# Enclosure_130x95_BP-R.net
KiCad netlist of a schematic drawn in EAGLE
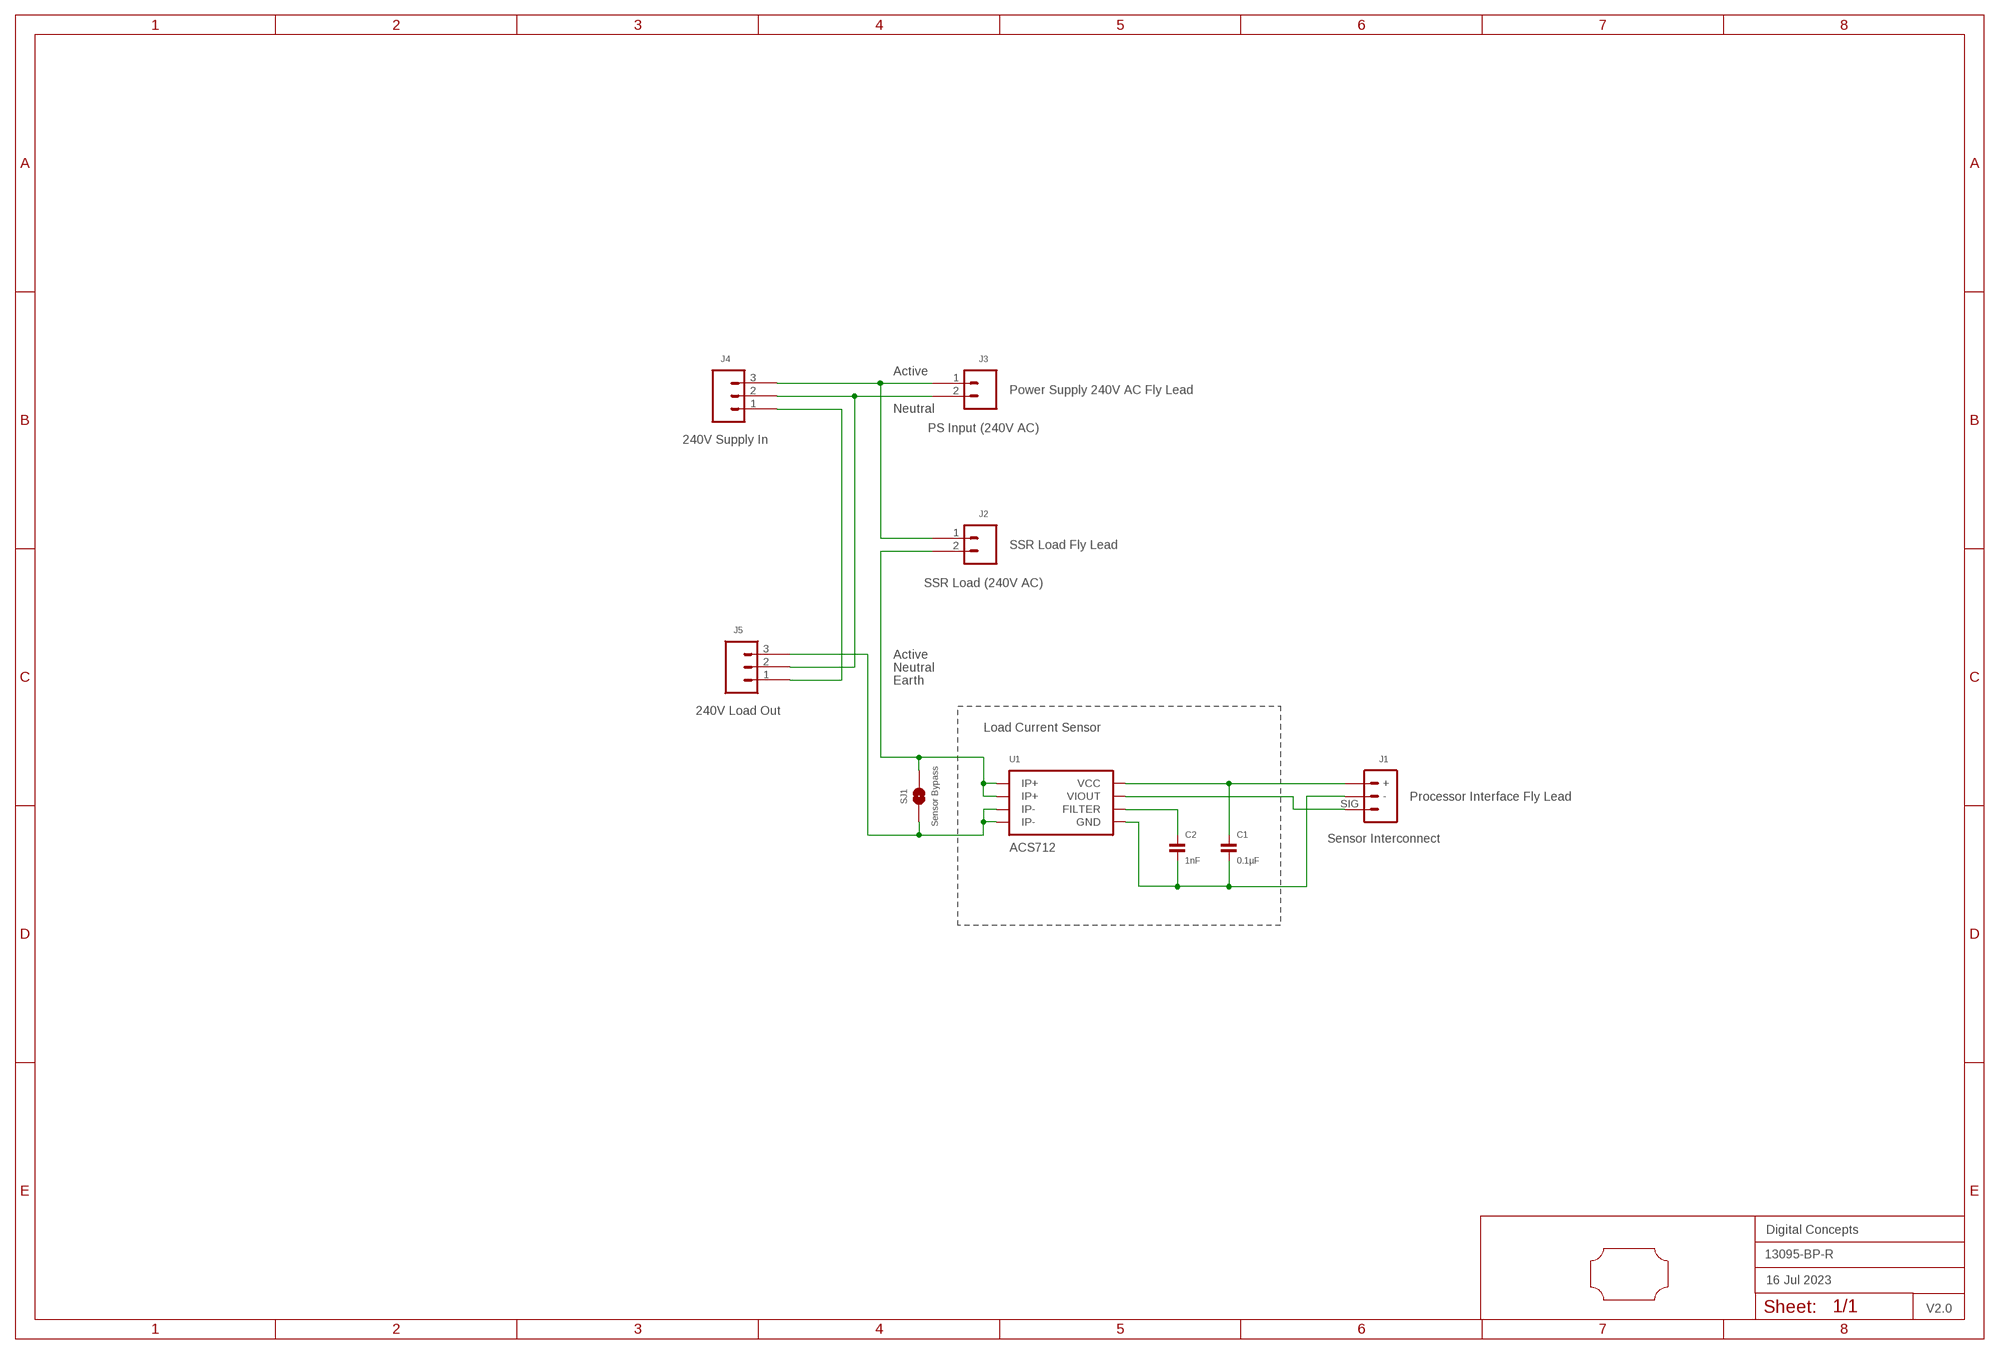
[diagram p0: schematic, sheet 1]

(export (version "E")
  (design (tool "Eeschema 10.0.6"))
  (components
    (comp (ref "C1")
      (value "0.1µF")
      (footprint "eagle-import:C0805")
      (libsource (lib "eagle-import") (part "CAPACITOR-0805"))
    )
    (comp (ref "C2")
      (value "1nF")
      (footprint "eagle-import:C0805")
      (libsource (lib "eagle-import") (part "CAPACITOR-0805"))
    )
    (comp (ref "J1")
      (value "Sensor Interconnect")
      (footprint "eagle-import:JST-PH2.0-3-HORIZONTAL-SIG")
      (libsource (lib "eagle-import") (part "JST-PH2.0-3-HORIZONTAL"))
    )
    (comp (ref "J2")
      (value "SSR Load (240V AC)")
      (footprint "eagle-import:TERMINAL-SCREW-2P")
      (libsource (lib "eagle-import") (part "TERMINAL_SCREW_2P_VERTICAL"))
    )
    (comp (ref "J3")
      (value "PS Input (240V AC)")
      (footprint "eagle-import:JST-XH2.4-2-HORIZONTAL")
      (libsource (lib "eagle-import") (part "JST-XH2.54-2-HORIZONTAL"))
    )
    (comp (ref "J4")
      (value "240V Supply In")
      (footprint "eagle-import:TERMINAL-SCREW-3P")
      (libsource (lib "eagle-import") (part "TERMINAL_SCREW_3P_VERTICAL"))
    )
    (comp (ref "J5")
      (value "240V Load Out")
      (footprint "eagle-import:TERMINAL-SCREW-3P")
      (libsource (lib "eagle-import") (part "TERMINAL_SCREW_3P_VERTICAL"))
    )
    (comp (ref "SJ1")
      (value "Sensor Bypass")
      (footprint "eagle-import:SJ")
      (libsource (lib "eagle-import") (part "SJ"))
    )
    (comp (ref "U$1")
      (value "PCB-OUTLINE-130X95-MAX-RC-H2")
      (footprint "eagle-import:PROTO-130X95-OUTLINE-MAX-RC-H2")
      (libsource (lib "eagle-import") (part "PCB-OUTLINE-130X95-MAX-RC-H2"))
    )
    (comp (ref "U1")
      (value "ACS712")
      (footprint "eagle-import:SOIC-8")
      (libsource (lib "eagle-import") (part "ACS712"))
    )
  )
  (nets
    (net (code "1") (name "Net-(J2-Pad1)") (class "Default")
      (node (ref "J2") (pin "1") (pinfunction "1_1") (pintype "passive"))
      (node (ref "J3") (pin "1") (pinfunction "1_1") (pintype "passive"))
      (node (ref "J4") (pin "3") (pinfunction "3_3") (pintype "passive"))
    )
    (net (code "2") (name "Net-(J2-Pad2)") (class "Default")
      (node (ref "J2") (pin "2") (pinfunction "2_2") (pintype "passive"))
      (node (ref "SJ1") (pin "2") (pinfunction "2_2") (pintype "passive"))
      (node (ref "U1") (pin "P$1") (pinfunction "IP+_P$1") (pintype "bidirectional"))
      (node (ref "U1") (pin "P$2") (pinfunction "IP+_P$2") (pintype "bidirectional"))
    )
    (net (code "3") (name "Net-(J3-Pad2)") (class "Default")
      (node (ref "J3") (pin "2") (pinfunction "2_2") (pintype "passive"))
      (node (ref "J4") (pin "2") (pinfunction "2_2") (pintype "passive"))
      (node (ref "J5") (pin "2") (pinfunction "2_2") (pintype "passive"))
    )
    (net (code "4") (name "Net-(J4-Pad1)") (class "Default")
      (node (ref "J4") (pin "1") (pinfunction "1_1") (pintype "passive"))
      (node (ref "J5") (pin "1") (pinfunction "1_1") (pintype "passive"))
    )
    (net (code "5") (name "Net-(J5-Pad3)") (class "Default")
      (node (ref "J5") (pin "3") (pinfunction "3_3") (pintype "passive"))
      (node (ref "SJ1") (pin "1") (pinfunction "1_1") (pintype "passive"))
      (node (ref "U1") (pin "P$3") (pinfunction "IP-_P$3") (pintype "bidirectional"))
      (node (ref "U1") (pin "P$4") (pinfunction "IP-_P$4") (pintype "bidirectional"))
    )
    (net (code "6") (name "Net-(U1-FILTER)") (class "Default")
      (node (ref "C2") (pin "1") (pinfunction "1_1") (pintype "passive"))
      (node (ref "U1") (pin "P$6") (pinfunction "FILTER_P$6") (pintype "bidirectional"))
    )
    (net (code "7") (name "Net-(U1-GND)") (class "Default")
      (node (ref "C1") (pin "2") (pinfunction "2_2") (pintype "passive"))
      (node (ref "C2") (pin "2") (pinfunction "2_2") (pintype "passive"))
      (node (ref "J1") (pin "-") (pinfunction "-_-") (pintype "power_in"))
      (node (ref "U1") (pin "P$5") (pinfunction "GND_P$5") (pintype "power_in"))
    )
    (net (code "8") (name "Net-(U1-VCC)") (class "Default")
      (node (ref "C1") (pin "1") (pinfunction "1_1") (pintype "passive"))
      (node (ref "J1") (pin "+") (pinfunction "+_+") (pintype "power_in"))
      (node (ref "U1") (pin "P$8") (pinfunction "VCC_P$8") (pintype "power_in"))
    )
    (net (code "9") (name "Net-(U1-VIOUT)") (class "Default")
      (node (ref "J1") (pin "SIG") (pinfunction "SIG_SIG") (pintype "bidirectional"))
      (node (ref "U1") (pin "P$7") (pinfunction "VIOUT_P$7") (pintype "bidirectional"))
    )
  )
)
